# nonregulation-level-shifter-mk-2_4.net
KiCad netlist of a schematic drawn in EAGLE
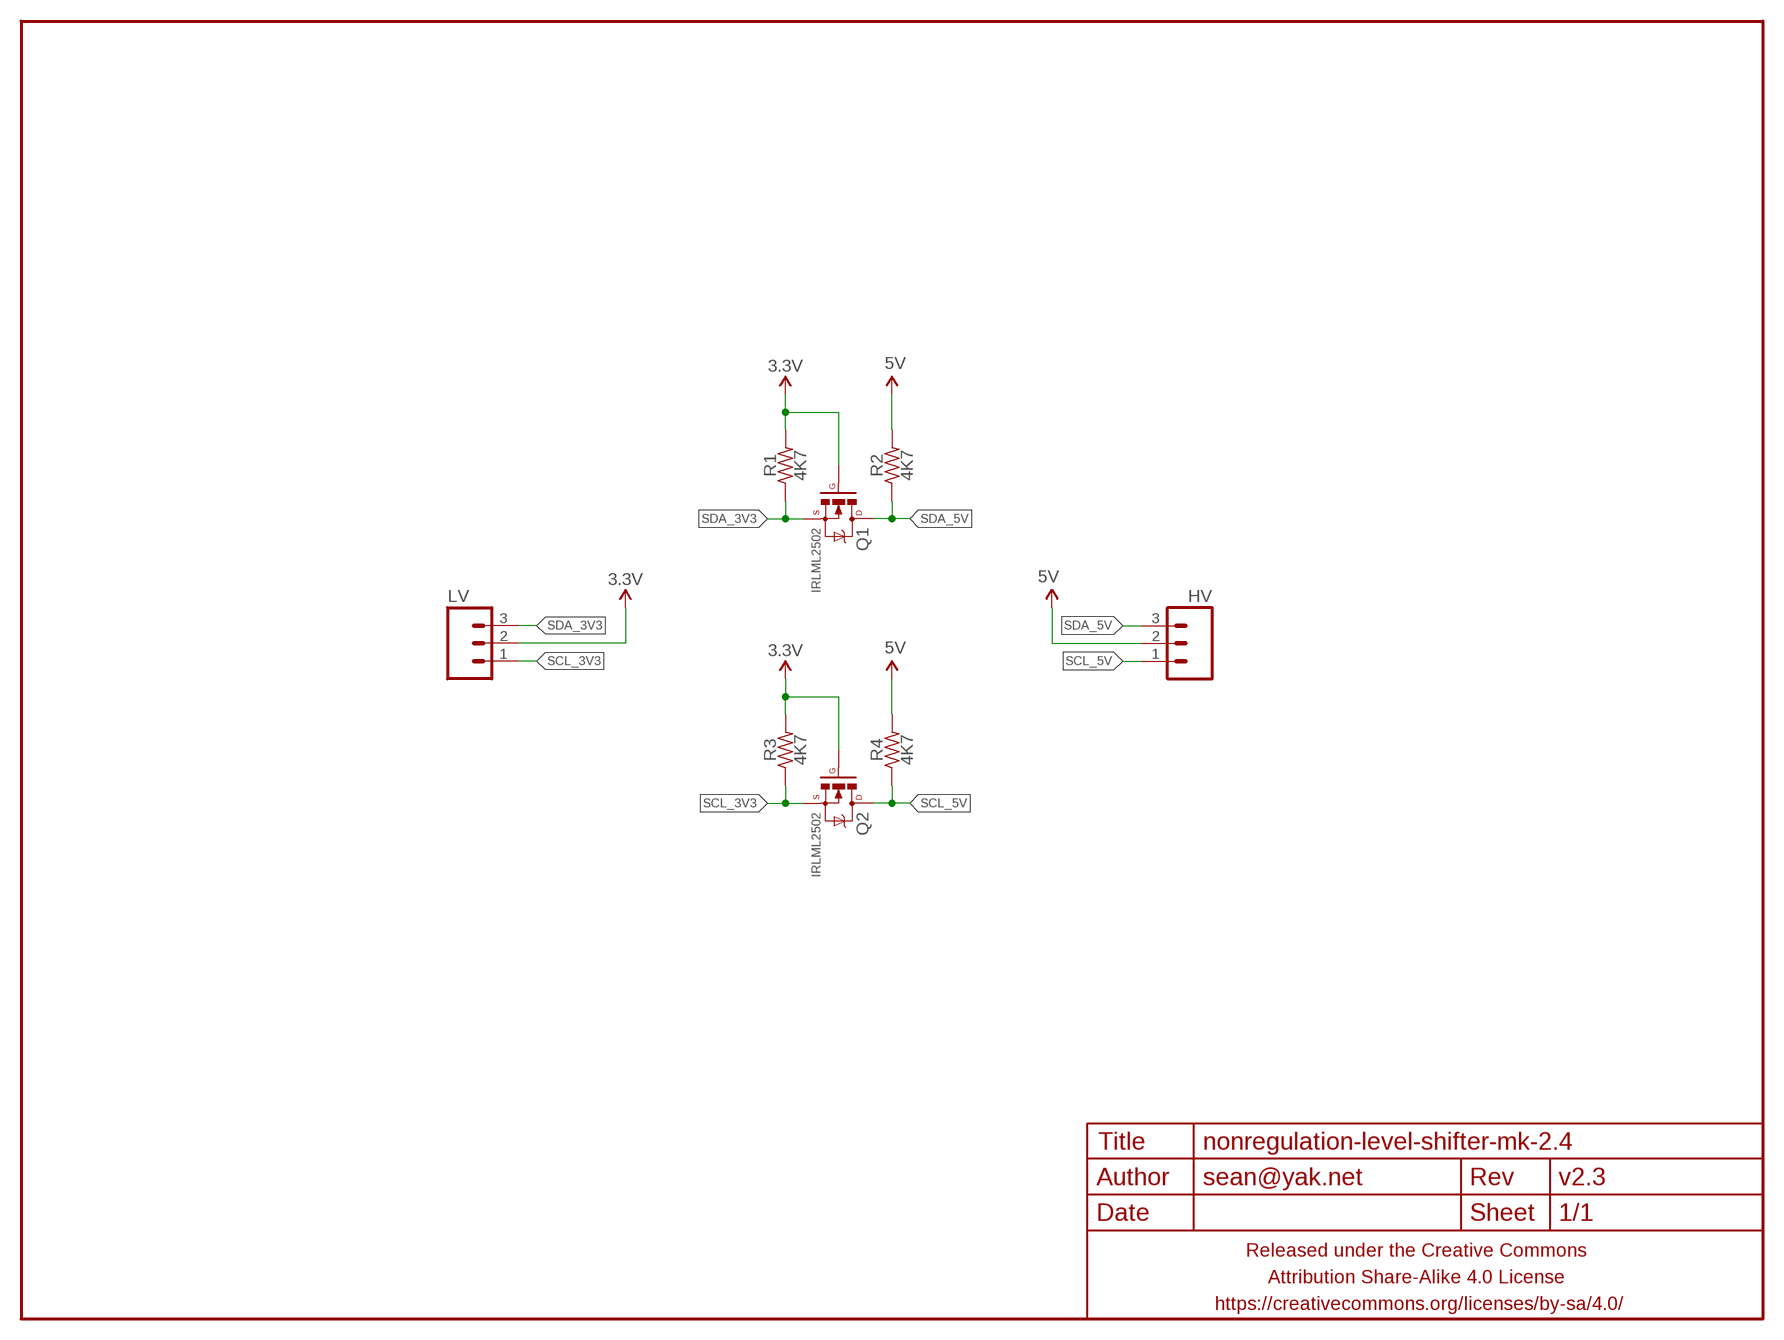
[diagram p0: schematic, sheet 1]

(export (version "E")
  (design (tool "Eeschema 10.0.6"))
  (components
    (comp (ref "FRAME1")
      (value "FRAME-LETTERNO_PACKAGE")
      (footprint "eagle-import:DUMMY")
      (fields (field (name "DESIGNER") "sean@yak.net") (field (name "VERSION") "v2.3"))
      (libsource (lib "eagle-import") (part "FRAME-LETTERNO_PACKAGE"))
    )
    (comp (ref "HV")
      (value "M03PTH-CENTERED")
      (footprint "eagle-import:1X03-CENTERED")
      (libsource (lib "eagle-import") (part "M03PTH-CENTERED"))
    )
    (comp (ref "LV")
      (value "M03PTH-CENTERED")
      (footprint "eagle-import:1X03-CENTERED")
      (libsource (lib "eagle-import") (part "M03PTH-CENTERED"))
    )
    (comp (ref "Q1")
      (value "IRLML2502")
      (footprint "eagle-import:SOT23")
      (libsource (lib "eagle-import") (part "MOSFET-NCHANNELIRLML2502"))
    )
    (comp (ref "Q2")
      (value "IRLML2502")
      (footprint "eagle-import:SOT23")
      (libsource (lib "eagle-import") (part "MOSFET-NCHANNELIRLML2502"))
    )
    (comp (ref "R1")
      (value "4K7")
      (footprint "eagle-import:R0603-TIGHTER")
      (libsource (lib "eagle-import") (part "RESISTORR0603-TIGHTER"))
    )
    (comp (ref "R2")
      (value "4K7")
      (footprint "eagle-import:R0603-TIGHTER")
      (libsource (lib "eagle-import") (part "RESISTORR0603-TIGHTER"))
    )
    (comp (ref "R3")
      (value "4K7")
      (footprint "eagle-import:R0603")
      (libsource (lib "eagle-import") (part "RESISTORR0603"))
    )
    (comp (ref "R4")
      (value "4K7")
      (footprint "eagle-import:R0603-TIGHTER")
      (libsource (lib "eagle-import") (part "RESISTORR0603-TIGHTER"))
    )
  )
  (nets
    (net (code "1") (name "3.3V") (class "Default")
      (node (ref "LV") (pin "2") (pinfunction "2_2") (pintype "passive"))
      (node (ref "Q1") (pin "1") (pinfunction "G_1") (pintype "passive"))
      (node (ref "Q2") (pin "1") (pinfunction "G_1") (pintype "passive"))
      (node (ref "R1") (pin "2") (pinfunction "2_2") (pintype "passive"))
      (node (ref "R3") (pin "2") (pinfunction "2_2") (pintype "passive"))
    )
    (net (code "2") (name "5V") (class "Default")
      (node (ref "HV") (pin "2") (pinfunction "2_2") (pintype "passive"))
      (node (ref "R2") (pin "2") (pinfunction "2_2") (pintype "passive"))
      (node (ref "R4") (pin "2") (pinfunction "2_2") (pintype "passive"))
    )
    (net (code "3") (name "SCL_3V3") (class "Default")
      (node (ref "LV") (pin "1") (pinfunction "1_1") (pintype "passive"))
      (node (ref "Q2") (pin "2") (pinfunction "S_2") (pintype "passive"))
      (node (ref "R3") (pin "1") (pinfunction "1_1") (pintype "passive"))
    )
    (net (code "4") (name "SCL_5V") (class "Default")
      (node (ref "HV") (pin "1") (pinfunction "1_1") (pintype "passive"))
      (node (ref "Q2") (pin "3") (pinfunction "D_3") (pintype "passive"))
      (node (ref "R4") (pin "1") (pinfunction "1_1") (pintype "passive"))
    )
    (net (code "5") (name "SDA_3V3") (class "Default")
      (node (ref "LV") (pin "3") (pinfunction "3_3") (pintype "passive"))
      (node (ref "Q1") (pin "2") (pinfunction "S_2") (pintype "passive"))
      (node (ref "R1") (pin "1") (pinfunction "1_1") (pintype "passive"))
    )
    (net (code "6") (name "SDA_5V") (class "Default")
      (node (ref "HV") (pin "3") (pinfunction "3_3") (pintype "passive"))
      (node (ref "Q1") (pin "3") (pinfunction "D_3") (pintype "passive"))
      (node (ref "R2") (pin "1") (pinfunction "1_1") (pintype "passive"))
    )
  )
)
